# LANA_TNY_01.net
KiCad netlist of a schematic drawn in Altium Designer
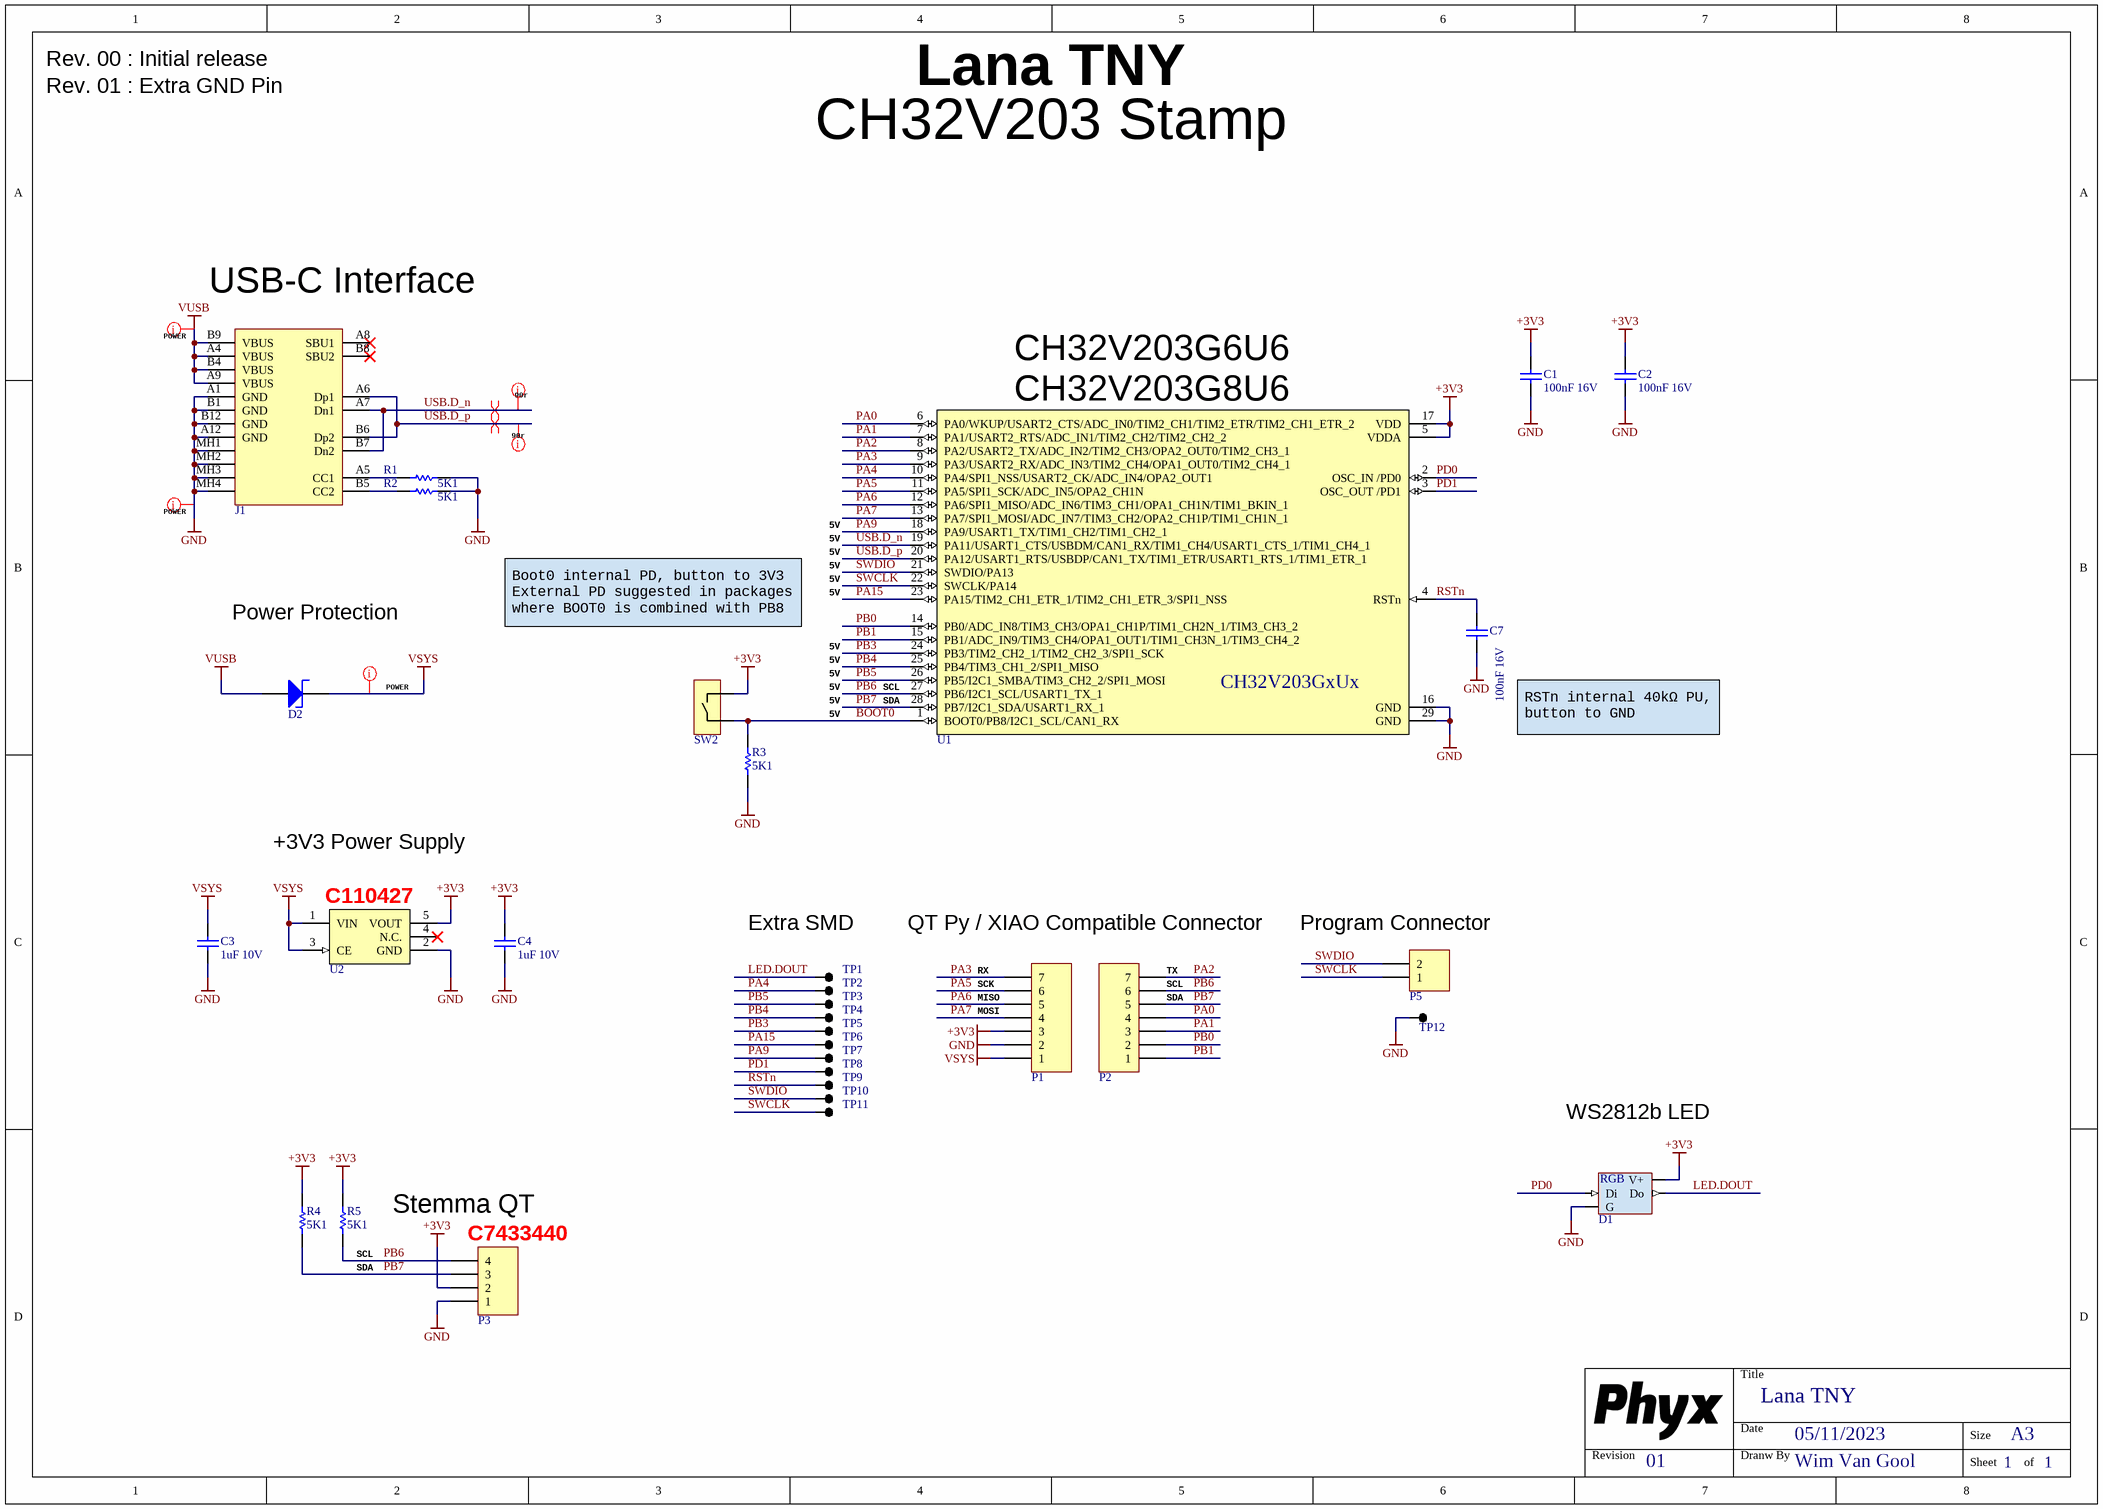
[diagram p0: LANA_TNY_01.SchDoc]

(export (version "E")
  (design (tool "Eeschema 10.0.6"))
  (components
    (comp (ref "C1")
      (value "100nF 16V")
      (footprint "C0402")
      (description "Capacitor Ceramic")
      (fields (field (name "Comment") "CAP_CERAMIC"))
      (libsource (lib "Phyx_Components") (part "CAP_CERAMIC"))
    )
    (comp (ref "C2")
      (value "100nF 16V")
      (footprint "C0402")
      (description "Capacitor Ceramic")
      (fields (field (name "Comment") "CAP_CERAMIC"))
      (libsource (lib "Phyx_Components") (part "CAP_CERAMIC"))
    )
    (comp (ref "C3")
      (value "1uF 10V")
      (footprint "C0402")
      (description "Capacitor Ceramic")
      (fields (field (name "Comment") "CAP_CERAMIC"))
      (libsource (lib "Phyx_Components") (part "CAP_CERAMIC"))
    )
    (comp (ref "C4")
      (value "1uF 10V")
      (footprint "C0402")
      (description "Capacitor Ceramic")
      (fields (field (name "Comment") "CAP_CERAMIC"))
      (libsource (lib "Phyx_Components") (part "CAP_CERAMIC"))
    )
    (comp (ref "C7")
      (value "100nF 16V")
      (footprint "C0402")
      (description "Capacitor Ceramic")
      (fields (field (name "Comment") "CAP_CERAMIC"))
      (libsource (lib "Phyx_Components") (part "CAP_CERAMIC"))
    )
    (comp (ref "D1")
      (value "WS2812 based digital RGB LED 1010 package")
      (footprint "LED_1010_WS2812B")
      (description "=Description")
      (libsource (lib "Phyx_Components") (part "LED_RGB_WS2812B_1010"))
    )
    (comp (ref "D2")
      (value "CUS10S30 Schottky Power Rectifier, 1A, 30V")
      (footprint "SOD-323_AC")
      (description "=Description")
      (libsource (lib "Phyx_Components") (part "Schottky_AC"))
    )
    (comp (ref "J1")
      (value "USB 2.0 C Reversible Receptacle Horizontal full SMD")
      (footprint "XUNPU-TYPEC-304S-ACP16")
      (libsource (lib "Phyx_Components") (part "USB_C_16_4"))
    )
    (comp (ref "P1")
      (value "Header 7")
      (footprint "HDR1X7")
      (libsource (lib "Phyx_Components") (part "Header 7"))
    )
    (comp (ref "P2") (value "Header 7") (footprint "HDR1X7") (libsource (lib "") (part "Header 7_1")))
    (comp (ref "P3")
      (value "Header 1.0mm Shrouded 4")
      (footprint "WE_665304124022")
      (libsource (lib "Phyx_Components") (part "Header 4"))
    )
    (comp (ref "P5")
      (value "Header 2")
      (footprint "HDR1X2")
      (libsource (lib "Phyx_Components") (part "Header 2"))
    )
    (comp (ref "R1")
      (value "5K1")
      (footprint "R0402")
      (fields (field (name "Comment") "RESISTOR"))
      (libsource (lib "Phyx_Components") (part "RESISTOR"))
    )
    (comp (ref "R2")
      (value "5K1")
      (footprint "R0402")
      (fields (field (name "Comment") "RESISTOR"))
      (libsource (lib "Phyx_Components") (part "RESISTOR"))
    )
    (comp (ref "R3")
      (value "5K1")
      (footprint "R0402")
      (fields (field (name "Comment") "RESISTOR"))
      (libsource (lib "Phyx_Components") (part "RESISTOR"))
    )
    (comp (ref "R4")
      (value "5K1")
      (footprint "R0402")
      (fields (field (name "Comment") "RESISTOR"))
      (libsource (lib "Phyx_Components") (part "RESISTOR"))
    )
    (comp (ref "R5")
      (value "5K1")
      (footprint "R0402")
      (fields (field (name "Comment") "RESISTOR"))
      (libsource (lib "Phyx_Components") (part "RESISTOR"))
    )
    (comp (ref "SW2")
      (value "TS24CA RA Tactile Switch 12V 50mA")
      (footprint "SHOU_HAN_TS24CA")
      (libsource (lib "Phyx_Components") (part "SW_TACT"))
    )
    (comp (ref "TP1")
      (value "TEST_PAD")
      (footprint "TP_0.4mm")
      (libsource (lib "Phyx_Components") (part "TEST_PAD"))
    )
    (comp (ref "TP2")
      (value "TEST_PAD")
      (footprint "TP_0.4mm")
      (libsource (lib "Phyx_Components") (part "TEST_PAD"))
    )
    (comp (ref "TP3")
      (value "TEST_PAD")
      (footprint "TP_0.4mm")
      (libsource (lib "Phyx_Components") (part "TEST_PAD"))
    )
    (comp (ref "TP4")
      (value "TEST_PAD")
      (footprint "TP_0.4mm")
      (libsource (lib "Phyx_Components") (part "TEST_PAD"))
    )
    (comp (ref "TP5")
      (value "TEST_PAD")
      (footprint "TP_0.4mm")
      (libsource (lib "Phyx_Components") (part "TEST_PAD"))
    )
    (comp (ref "TP6")
      (value "TEST_PAD")
      (footprint "TP_0.4mm")
      (libsource (lib "Phyx_Components") (part "TEST_PAD"))
    )
    (comp (ref "TP7")
      (value "TEST_PAD")
      (footprint "TP_0.4mm")
      (libsource (lib "Phyx_Components") (part "TEST_PAD"))
    )
    (comp (ref "TP8")
      (value "TEST_PAD")
      (footprint "TP_0.4mm")
      (libsource (lib "Phyx_Components") (part "TEST_PAD"))
    )
    (comp (ref "TP9")
      (value "TEST_PAD")
      (footprint "TP_0.4mm")
      (libsource (lib "Phyx_Components") (part "TEST_PAD"))
    )
    (comp (ref "TP10")
      (value "TEST_PAD")
      (footprint "TP_0.4mm")
      (libsource (lib "Phyx_Components") (part "TEST_PAD"))
    )
    (comp (ref "TP11")
      (value "TEST_PAD")
      (footprint "TP_0.4mm")
      (libsource (lib "Phyx_Components") (part "TEST_PAD"))
    )
    (comp (ref "TP12")
      (value "TEST_PAD")
      (footprint "TP_1.2mm_0.6mm")
      (description "TP 1.2mm")
      (libsource (lib "Phyx_Components") (part "TEST_PAD"))
    )
    (comp (ref "U1")
      (value "WCH CH32V203G8U6 QFN28 RISC-V 32-bit MCU, 64KB Flash, 20KB RAM, USB, CAN")
      (footprint "QFN_28_4.0x4.0_P0.4")
      (libsource (lib "Phyx_Components") (part "WCH_CH32V203GxUx"))
    )
    (comp (ref "U2")
      (value "3V3 LDO 300mA 150mV")
      (footprint "SOT23-5")
      (description "=Designator")
      (libsource (lib "Phyx_Components") (part "XC6210_SOT"))
    )
  )
  (nets
    (net (code "1") (name "+3V3") (class "Default")
      (node (ref "C1") (pin "1") (pinfunction "1_1") (pintype "passive"))
      (node (ref "C2") (pin "1") (pinfunction "1_1") (pintype "passive"))
      (node (ref "C4") (pin "1") (pinfunction "1_1") (pintype "passive"))
      (node (ref "D1") (pin "2") (pinfunction "V+_2") (pintype "power_in"))
      (node (ref "P1") (pin "3") (pinfunction "3_3") (pintype "passive"))
      (node (ref "P3") (pin "2") (pinfunction "2_2") (pintype "passive"))
      (node (ref "R4") (pin "1") (pinfunction "1_1") (pintype "passive"))
      (node (ref "R5") (pin "1") (pinfunction "1_1") (pintype "passive"))
      (node (ref "SW2") (pin "1") (pinfunction "1_1") (pintype "passive"))
      (node (ref "U1") (pin "17") (pinfunction "VDD_17") (pintype "power_in"))
      (node (ref "U1") (pin "5") (pinfunction "VDDA_5") (pintype "power_in"))
      (node (ref "U2") (pin "5") (pinfunction "VOUT_5") (pintype "power_in"))
    )
    (net (code "2") (name "/BOOT0") (class "Default")
      (node (ref "R3") (pin "1") (pinfunction "1_1") (pintype "passive"))
      (node (ref "SW2") (pin "2") (pinfunction "2_2") (pintype "passive"))
      (node (ref "U1") (pin "1") (pinfunction "BOOT0/PB8/I2C1_SCL/CAN1_RX_1") (pintype "bidirectional"))
    )
    (net (code "3") (name "/LED.DOUT") (class "Default")
      (node (ref "D1") (pin "1") (pinfunction "Do_1") (pintype "output"))
      (node (ref "TP1") (pin "1") (pinfunction "1_1") (pintype "passive"))
    )
    (net (code "4") (name "/PA0") (class "Default")
      (node (ref "P2") (pin "4") (pinfunction "4_4") (pintype "passive"))
      (node (ref "U1") (pin "6") (pinfunction "PA0/WKUP/USART2_CTS/ADC_IN0/TIM2_CH1/TIM2_ETR/TIM2_CH1_ETR_2_6") (pintype "bidirectional"))
    )
    (net (code "5") (name "/PA1") (class "Default")
      (node (ref "P2") (pin "3") (pinfunction "3_3") (pintype "passive"))
      (node (ref "U1") (pin "7") (pinfunction "PA1/USART2_RTS/ADC_IN1/TIM2_CH2/TIM2_CH2_2_7") (pintype "bidirectional"))
    )
    (net (code "6") (name "/PA2") (class "Default")
      (node (ref "P2") (pin "7") (pinfunction "7_7") (pintype "passive"))
      (node (ref "U1") (pin "8") (pinfunction "PA2/USART2_TX/ADC_IN2/TIM2_CH3/OPA2_OUT0/TIM2_CH3_1_8") (pintype "bidirectional"))
    )
    (net (code "7") (name "/PA3") (class "Default")
      (node (ref "P1") (pin "7") (pinfunction "7_7") (pintype "passive"))
      (node (ref "U1") (pin "9") (pinfunction "PA3/USART2_RX/ADC_IN3/TIM2_CH4/OPA1_OUT0/TIM2_CH4_1_9") (pintype "bidirectional"))
    )
    (net (code "8") (name "/PA4") (class "Default")
      (node (ref "TP2") (pin "1") (pinfunction "1_1") (pintype "passive"))
      (node (ref "U1") (pin "10") (pinfunction "PA4/SPI1_NSS/USART2_CK/ADC_IN4/OPA2_OUT1_10") (pintype "bidirectional"))
    )
    (net (code "9") (name "/PA5") (class "Default")
      (node (ref "P1") (pin "6") (pinfunction "6_6") (pintype "passive"))
      (node (ref "U1") (pin "11") (pinfunction "PA5/SPI1_SCK/ADC_IN5/OPA2_CH1N_11") (pintype "bidirectional"))
    )
    (net (code "10") (name "/PA6") (class "Default")
      (node (ref "P1") (pin "5") (pinfunction "5_5") (pintype "passive"))
      (node (ref "U1") (pin "12") (pinfunction "PA6/SPI1_MISO/ADC_IN6/TIM3_CH1/OPA1_CH1N/TIM1_BKIN_1_12") (pintype "bidirectional"))
    )
    (net (code "11") (name "/PA7") (class "Default")
      (node (ref "P1") (pin "4") (pinfunction "4_4") (pintype "passive"))
      (node (ref "U1") (pin "13") (pinfunction "PA7/SPI1_MOSI/ADC_IN7/TIM3_CH2/OPA2_CH1P/TIM1_CH1N_1_13") (pintype "bidirectional"))
    )
    (net (code "12") (name "/PA9") (class "Default")
      (node (ref "TP7") (pin "1") (pinfunction "1_1") (pintype "passive"))
      (node (ref "U1") (pin "18") (pinfunction "PA9/USART1_TX/TIM1_CH2/TIM1_CH2_1_18") (pintype "bidirectional"))
    )
    (net (code "13") (name "/PA15") (class "Default")
      (node (ref "TP6") (pin "1") (pinfunction "1_1") (pintype "passive"))
      (node (ref "U1") (pin "23") (pinfunction "PA15/TIM2_CH1_ETR_1/TIM2_CH1_ETR_3/SPI1_NSS_23") (pintype "bidirectional"))
    )
    (net (code "14") (name "/PB0") (class "Default")
      (node (ref "P2") (pin "2") (pinfunction "2_2") (pintype "passive"))
      (node (ref "U1") (pin "14") (pinfunction "PB0/ADC_IN8/TIM3_CH3/OPA1_CH1P/TIM1_CH2N_1/TIM3_CH3_2_14") (pintype "bidirectional"))
    )
    (net (code "15") (name "/PB1") (class "Default")
      (node (ref "P2") (pin "1") (pinfunction "1_1") (pintype "passive"))
      (node (ref "U1") (pin "15") (pinfunction "PB1/ADC_IN9/TIM3_CH4/OPA1_OUT1/TIM1_CH3N_1/TIM3_CH4_2_15") (pintype "bidirectional"))
    )
    (net (code "16") (name "/PB3") (class "Default")
      (node (ref "TP5") (pin "1") (pinfunction "1_1") (pintype "passive"))
      (node (ref "U1") (pin "24") (pinfunction "PB3/TIM2_CH2_1/TIM2_CH2_3/SPI1_SCK_24") (pintype "bidirectional"))
    )
    (net (code "17") (name "/PB4") (class "Default")
      (node (ref "TP4") (pin "1") (pinfunction "1_1") (pintype "passive"))
      (node (ref "U1") (pin "25") (pinfunction "PB4/TIM3_CH1_2/SPI1_MISO_25") (pintype "bidirectional"))
    )
    (net (code "18") (name "/PB5") (class "Default")
      (node (ref "TP3") (pin "1") (pinfunction "1_1") (pintype "passive"))
      (node (ref "U1") (pin "26") (pinfunction "PB5/I2C1_SMBA/TIM3_CH2_2/SPI1_MOSI_26") (pintype "bidirectional"))
    )
    (net (code "19") (name "/PB6") (class "Default")
      (node (ref "P2") (pin "6") (pinfunction "6_6") (pintype "passive"))
      (node (ref "P3") (pin "4") (pinfunction "4_4") (pintype "passive"))
      (node (ref "R5") (pin "2") (pinfunction "2_2") (pintype "passive"))
      (node (ref "U1") (pin "27") (pinfunction "PB6/I2C1_SCL/USART1_TX_1_27") (pintype "bidirectional"))
    )
    (net (code "20") (name "/PB7") (class "Default")
      (node (ref "P2") (pin "5") (pinfunction "5_5") (pintype "passive"))
      (node (ref "P3") (pin "3") (pinfunction "3_3") (pintype "passive"))
      (node (ref "R4") (pin "2") (pinfunction "2_2") (pintype "passive"))
      (node (ref "U1") (pin "28") (pinfunction "PB7/I2C1_SDA/USART1_RX_1_28") (pintype "bidirectional"))
    )
    (net (code "21") (name "/PD0") (class "Default")
      (node (ref "D1") (pin "4") (pinfunction "Di_4") (pintype "input"))
      (node (ref "U1") (pin "2") (pinfunction "OSC_IN_/PD0_2") (pintype "bidirectional"))
    )
    (net (code "22") (name "/PD1") (class "Default")
      (node (ref "TP8") (pin "1") (pinfunction "1_1") (pintype "passive"))
      (node (ref "U1") (pin "3") (pinfunction "OSC_OUT_/PD1_3") (pintype "bidirectional"))
    )
    (net (code "23") (name "/RSTn") (class "Default")
      (node (ref "C7") (pin "1") (pinfunction "1_1") (pintype "passive"))
      (node (ref "TP9") (pin "1") (pinfunction "1_1") (pintype "passive"))
      (node (ref "U1") (pin "4") (pinfunction "RSTn_4") (pintype "input"))
    )
    (net (code "24") (name "/SWCLK") (class "Default")
      (node (ref "P5") (pin "1") (pinfunction "1_1") (pintype "passive"))
      (node (ref "TP11") (pin "1") (pinfunction "1_1") (pintype "passive"))
      (node (ref "U1") (pin "22") (pinfunction "SWCLK/PA14_22") (pintype "bidirectional"))
    )
    (net (code "25") (name "/SWDIO") (class "Default")
      (node (ref "P5") (pin "2") (pinfunction "2_2") (pintype "passive"))
      (node (ref "TP10") (pin "1") (pinfunction "1_1") (pintype "passive"))
      (node (ref "U1") (pin "21") (pinfunction "SWDIO/PA13_21") (pintype "bidirectional"))
    )
    (net (code "26") (name "/USB.D_n") (class "Default")
      (node (ref "J1") (pin "A7") (pinfunction "Dn1_A7") (pintype "passive"))
      (node (ref "J1") (pin "B7") (pinfunction "Dn2_B7") (pintype "passive"))
      (node (ref "U1") (pin "19") (pinfunction "PA11/USART1_CTS/USBDM/CAN1_RX/TIM1_CH4/USART1_CTS_1/TIM1_CH4_1_19") (pintype "bidirectional"))
    )
    (net (code "27") (name "/USB.D_p") (class "Default")
      (node (ref "J1") (pin "A6") (pinfunction "Dp1_A6") (pintype "passive"))
      (node (ref "J1") (pin "B6") (pinfunction "Dp2_B6") (pintype "passive"))
      (node (ref "U1") (pin "20") (pinfunction "PA12/USART1_RTS/USBDP/CAN1_TX/TIM1_ETR/USART1_RTS_1/TIM1_ETR_1_20") (pintype "bidirectional"))
    )
    (net (code "28") (name "GND") (class "Default")
      (node (ref "C1") (pin "2") (pinfunction "2_2") (pintype "passive"))
      (node (ref "C2") (pin "2") (pinfunction "2_2") (pintype "passive"))
      (node (ref "C3") (pin "2") (pinfunction "2_2") (pintype "passive"))
      (node (ref "C4") (pin "2") (pinfunction "2_2") (pintype "passive"))
      (node (ref "C7") (pin "2") (pinfunction "2_2") (pintype "passive"))
      (node (ref "D1") (pin "3") (pinfunction "G_3") (pintype "power_in"))
      (node (ref "J1") (pin "A1") (pinfunction "GND_A1") (pintype "passive"))
      (node (ref "J1") (pin "A12") (pinfunction "GND_A12") (pintype "passive"))
      (node (ref "J1") (pin "B1") (pinfunction "GND_B1") (pintype "passive"))
      (node (ref "J1") (pin "B12") (pinfunction "GND_B12") (pintype "passive"))
      (node (ref "J1") (pin "MH1") (pinfunction "Tab_MH1") (pintype "passive"))
      (node (ref "J1") (pin "MH2") (pinfunction "Tab_MH2") (pintype "passive"))
      (node (ref "J1") (pin "MH3") (pinfunction "Tab_MH3") (pintype "passive"))
      (node (ref "J1") (pin "MH4") (pinfunction "Tab_MH4") (pintype "passive"))
      (node (ref "P1") (pin "2") (pinfunction "2_2") (pintype "passive"))
      (node (ref "P3") (pin "1") (pinfunction "1_1") (pintype "passive"))
      (node (ref "R1") (pin "1") (pinfunction "1_1") (pintype "passive"))
      (node (ref "R2") (pin "1") (pinfunction "1_1") (pintype "passive"))
      (node (ref "R3") (pin "2") (pinfunction "2_2") (pintype "passive"))
      (node (ref "TP12") (pin "1") (pinfunction "1_1") (pintype "passive"))
      (node (ref "U1") (pin "16") (pinfunction "GND_16") (pintype "power_in"))
      (node (ref "U1") (pin "29") (pinfunction "GND_29") (pintype "power_in"))
      (node (ref "U2") (pin "2") (pinfunction "GND_2") (pintype "power_in"))
    )
    (net (code "29") (name "Net-(J1-CC1)") (class "Default")
      (node (ref "J1") (pin "A5") (pinfunction "CC1_A5") (pintype "passive"))
      (node (ref "R1") (pin "2") (pinfunction "2_2") (pintype "passive"))
    )
    (net (code "30") (name "Net-(J1-CC2)") (class "Default")
      (node (ref "J1") (pin "B5") (pinfunction "CC2_B5") (pintype "passive"))
      (node (ref "R2") (pin "2") (pinfunction "2_2") (pintype "passive"))
    )
    (net (code "31") (name "VSYS") (class "Default")
      (node (ref "C3") (pin "1") (pinfunction "1_1") (pintype "passive"))
      (node (ref "D2") (pin "C") (pinfunction "C_C") (pintype "passive"))
      (node (ref "P1") (pin "1") (pinfunction "1_1") (pintype "passive"))
      (node (ref "U2") (pin "1") (pinfunction "VIN_1") (pintype "power_in"))
      (node (ref "U2") (pin "3") (pinfunction "CE_3") (pintype "input"))
    )
    (net (code "32") (name "VUSB") (class "Default")
      (node (ref "D2") (pin "A") (pinfunction "A_A") (pintype "passive"))
      (node (ref "J1") (pin "A4") (pinfunction "VBUS_A4") (pintype "passive"))
      (node (ref "J1") (pin "A9") (pinfunction "VBUS_A9") (pintype "passive"))
      (node (ref "J1") (pin "B4") (pinfunction "VBUS_B4") (pintype "passive"))
      (node (ref "J1") (pin "B9") (pinfunction "VBUS_B9") (pintype "passive"))
    )
    (net (code "33") (name "unconnected-(J1-SBU1-PadA8)") (class "Default")
      (node (ref "J1") (pin "A8") (pinfunction "SBU1_A8") (pintype "passive+no_connect"))
    )
    (net (code "34") (name "unconnected-(J1-SBU2-PadB8)") (class "Default")
      (node (ref "J1") (pin "B8") (pinfunction "SBU2_B8") (pintype "passive+no_connect"))
    )
    (net (code "35") (name "unconnected-(U2-N.C.-Pad4)") (class "Default")
      (node (ref "U2") (pin "4") (pinfunction "N.C._4") (pintype "passive+no_connect"))
    )
  )
)
